# Power.net
KiCad netlist of a schematic drawn in Altium Designer
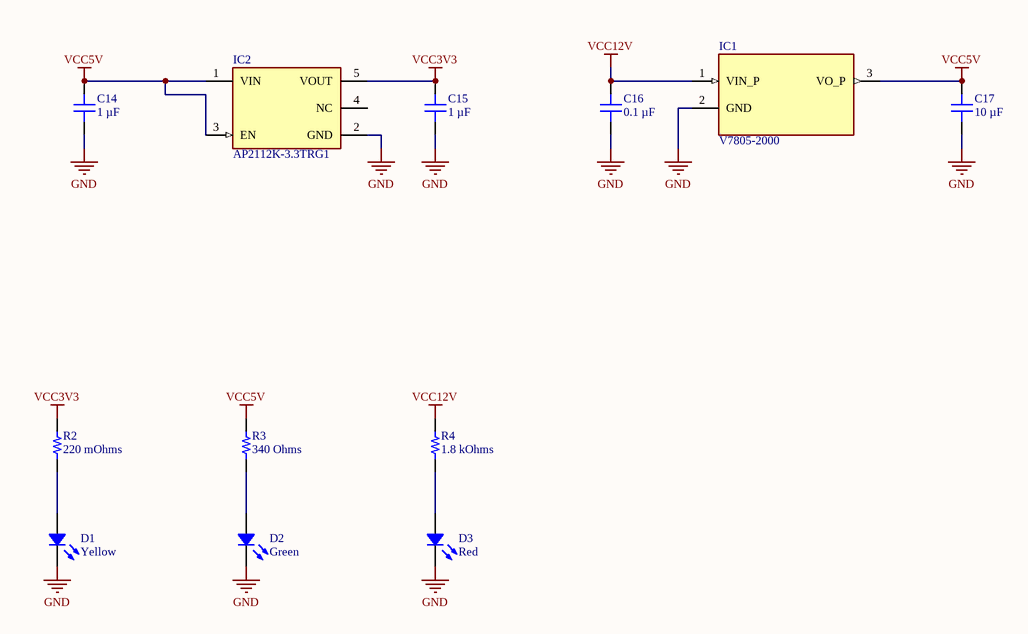
[diagram p0: Power.SchDoc]

(export (version "E")
  (design (tool "Eeschema 10.0.6"))
  (components
    (comp (ref "C14")
      (value "1 µF")
      (footprint "CAP 0201_0603")
      (description "CAP CER 1UF 6.3V X5R 0201")
      (fields
        (field (name "PART NUMBER") "CL03A105MQ3CSNC")
        (field (name "MANUFACTURER") "Samsung Electro-Mechanics")
      )
      (libsource (lib "Celestial Altium Library - altium_library") (part "Capacitor"))
    )
    (comp (ref "C15")
      (value "1 µF")
      (footprint "CAP 0201_0603")
      (description "CAP CER 1UF 6.3V X5R 0201")
      (fields
        (field (name "PART NUMBER") "CL03A105MQ3CSNC")
        (field (name "MANUFACTURER") "Samsung Electro-Mechanics")
      )
      (libsource (lib "Celestial Altium Library - altium_library") (part "Capacitor"))
    )
    (comp (ref "C16")
      (value "0.1 µF")
      (footprint "CAP 0201_0603")
      (description "CAP CER 0.1UF 16V X5R 0201")
      (fields (field (name "PART NUMBER") "EMK063BJ104MP-F") (field (name "MANUFACTURER") "Taiyo Yuden"))
      (libsource (lib "Celestial Altium Library - altium_library") (part "Capacitor"))
    )
    (comp (ref "C17")
      (value "10 µF")
      (footprint "CAP 0402_1005")
      (description "CAP CER 10UF 10V X5R 0402")
      (fields
        (field (name "PART NUMBER") "CL05A106MP8NUB8")
        (field (name "MANUFACTURER") "Samsung Electro-Mechanics")
      )
      (libsource (lib "Celestial Altium Library - altium_library") (part "Capacitor"))
    )
    (comp (ref "D1")
      (value "Yellow")
      (footprint "LED 1206_3216 YELLOW")
      (description "LED YELLOW CLEAR 2SMD")
      (fields
        (field (name "PART NUMBER") "25-21UYC/S530-A2/TR8")
        (field (name "MANUFACTURER") "Everlight Electronics Co Ltd")
      )
      (libsource (lib "Celestial Altium Library - altium_library") (part "LED"))
    )
    (comp (ref "D2")
      (value "Green")
      (footprint "LED 0805_2012 GREEN")
      (description "LED GREEN CLEAR 0805 SMD")
      (fields
        (field (name "PART NUMBER") "QTLP630C4TR")
        (field (name "MANUFACTURER") "Everlight Electronics Co Ltd")
      )
      (libsource (lib "Celestial Altium Library - altium_library") (part "LED"))
    )
    (comp (ref "D3")
      (value "Red")
      (footprint "LED 1206_3216 RED")
      (description "LED RED CLEAR 2SMD")
      (fields (field (name "PART NUMBER") "XZMDK55W-A2RT") (field (name "MANUFACTURER") "SunLED"))
      (libsource (lib "Celestial Altium Library - altium_library") (part "LED"))
    )
    (comp (ref "IC1")
      (value "V7805-2000")
      (footprint "CONV_V7805-2000")
      (description "2 A Output Current, 4.75~18 Vdc Input, 3 Pin SIP, Non-Isolated, Dc-Dc Converter")
      (fields (field (name "DIGI-KEY_PART_NUMBER") "102-2188-ND") (field (name "MF") "CUI Inc."))
      (libsource (lib "V7805-2000") (part "V7805-2000"))
    )
    (comp (ref "IC2")
      (value "AP2112K-3.3TRG1")
      (footprint "FP-SOT25-IPC_A")
      (description "IC REG LINEAR 3.3V 600MA SOT25")
      (libsource (lib "Altium Content Vault") (part "c8ab751aee5229183125ab046a11caa"))
    )
    (comp (ref "R2")
      (value "220 mOhms")
      (footprint "RES 0201_0603")
      (description "RES 0.22 OHM 1% 1/10W 0201")
      (fields
        (field (name "PART NUMBER") "UCR006YVPFLR220")
        (field (name "MANUFACTURER") "Rohm Semiconductor")
      )
      (libsource (lib "Celestial Altium Library - altium_library") (part "Resistor"))
    )
    (comp (ref "R3")
      (value "340 Ohms")
      (footprint "RES 0201_0603")
      (description "RES SMD 340 OHM 1% 1/20W 0201")
      (fields (field (name "PART NUMBER") "AC0201FR-07340RL") (field (name "MANUFACTURER") "Yageo"))
      (libsource (lib "Celestial Altium Library - altium_library") (part "Resistor"))
    )
    (comp (ref "R4")
      (value "1.8 kOhms")
      (footprint "RES 0201_0603")
      (description "RES SMD 1.8K OHM 5% 1/20W 0201")
      (fields (field (name "PART NUMBER") "CRCW02011K80JNED") (field (name "MANUFACTURER") "Vishay Dale"))
      (libsource (lib "Celestial Altium Library - altium_library") (part "Resistor"))
    )
  )
  (nets
    (net (code "1") (name "GND") (class "Default")
      (node (ref "C14") (pin "1") (pinfunction "1_1") (pintype "passive"))
      (node (ref "C15") (pin "1") (pinfunction "1_1") (pintype "passive"))
      (node (ref "C16") (pin "1") (pinfunction "1_1") (pintype "passive"))
      (node (ref "C17") (pin "1") (pinfunction "1_1") (pintype "passive"))
      (node (ref "D1") (pin "2") (pinfunction "2_2") (pintype "passive"))
      (node (ref "D2") (pin "2") (pinfunction "2_2") (pintype "passive"))
      (node (ref "D3") (pin "2") (pinfunction "2_2") (pintype "passive"))
      (node (ref "IC1") (pin "2") (pinfunction "GND_2") (pintype "power_in"))
      (node (ref "IC2") (pin "2") (pinfunction "GND_2") (pintype "power_in"))
    )
    (net (code "2") (name "Net-(D1-Pad1)") (class "Default")
      (node (ref "D1") (pin "1") (pinfunction "1_1") (pintype "passive"))
      (node (ref "R2") (pin "1") (pinfunction "1_1") (pintype "passive"))
    )
    (net (code "3") (name "Net-(D2-Pad1)") (class "Default")
      (node (ref "D2") (pin "1") (pinfunction "1_1") (pintype "passive"))
      (node (ref "R3") (pin "1") (pinfunction "1_1") (pintype "passive"))
    )
    (net (code "4") (name "Net-(D3-Pad1)") (class "Default")
      (node (ref "D3") (pin "1") (pinfunction "1_1") (pintype "passive"))
      (node (ref "R4") (pin "1") (pinfunction "1_1") (pintype "passive"))
    )
    (net (code "5") (name "VCC3V3") (class "Default")
      (node (ref "C15") (pin "2") (pinfunction "2_2") (pintype "passive"))
      (node (ref "IC2") (pin "5") (pinfunction "VOUT_5") (pintype "power_in"))
      (node (ref "R2") (pin "2") (pinfunction "2_2") (pintype "passive"))
    )
    (net (code "6") (name "VCC5V") (class "Default")
      (node (ref "C14") (pin "2") (pinfunction "2_2") (pintype "passive"))
      (node (ref "C17") (pin "2") (pinfunction "2_2") (pintype "passive"))
      (node (ref "IC1") (pin "3") (pinfunction "VO_P_3") (pintype "output"))
      (node (ref "IC2") (pin "1") (pinfunction "VIN_1") (pintype "power_in"))
      (node (ref "IC2") (pin "3") (pinfunction "EN_3") (pintype "input"))
      (node (ref "R3") (pin "2") (pinfunction "2_2") (pintype "passive"))
    )
    (net (code "7") (name "VCC12V") (class "Default")
      (node (ref "C16") (pin "2") (pinfunction "2_2") (pintype "passive"))
      (node (ref "IC1") (pin "1") (pinfunction "VIN_P_1") (pintype "input"))
      (node (ref "R4") (pin "2") (pinfunction "2_2") (pintype "passive"))
    )
    (net (code "8") (name "unconnected-(IC2-NC-Pad4)") (class "Default")
      (node (ref "IC2") (pin "4") (pinfunction "NC_4") (pintype "passive"))
    )
  )
)
